# Port_Def.net
KiCad netlist of a schematic drawn in Altium Designer
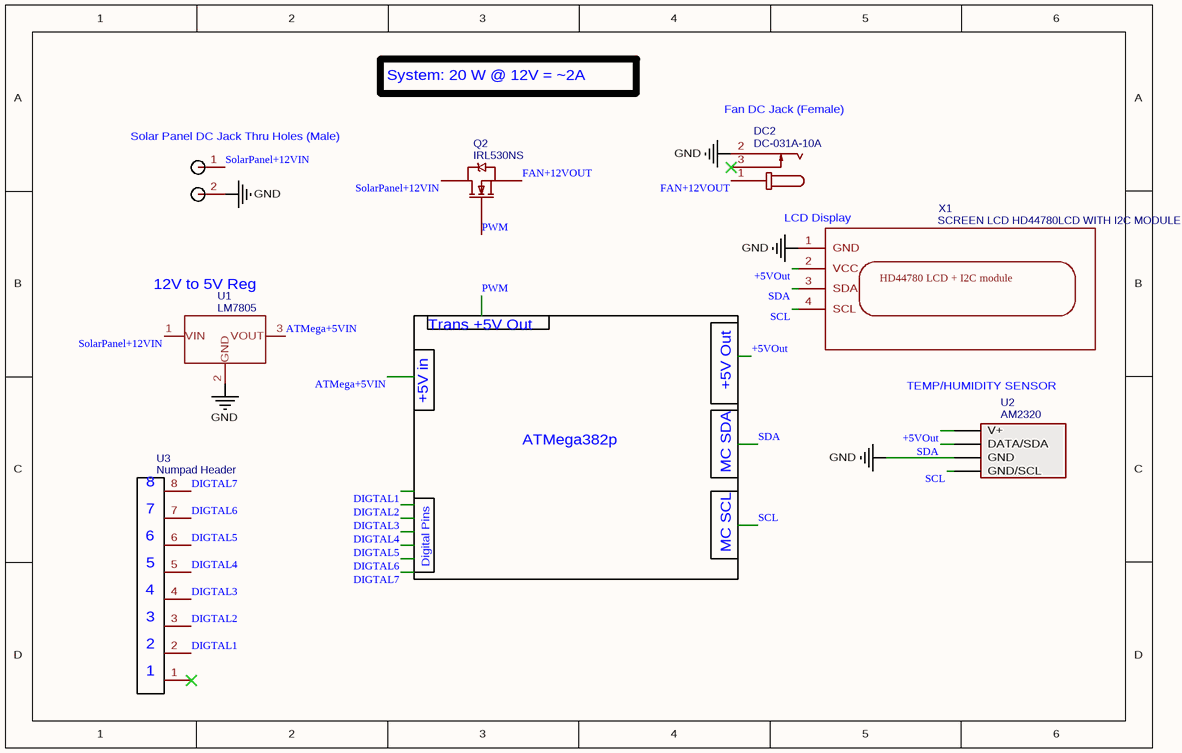
[diagram p0: Port Def.schdoc]

(export (version "E")
  (design (tool "Eeschema 10.0.6"))
  (components
    (comp (ref "DC2")
      (value "DC-031A-10A")
      (fields (field (name "BOM_SUPPLIER PART") "C145927") (field (name "CONTRIBUTOR") "LCSC"))
      (libsource (lib "altium-import") (part "root_2_DC-031A-10A_"))
    )
    (comp (ref "Q2")
      (value "IRL530NS")
      (description "HEXFET Power MOSFET")
      (libsource (lib "altium-import") (part "root_1_IRL530NS_"))
    )
    (comp (ref "U1")
      (value "LM7805")
      (description "DIP PMIC;LDO;Vin 7.5-20V;Adj;1A;Without En;1-Ch")
      (fields
        (field (name "BOM_SUPPLIER PART") "310030049")
        (field (name "BOM_MANUFACTURER PART") "LM7805ACT")
      )
      (libsource (lib "altium-import") (part "root_0_LM7805_"))
    )
    (comp (ref "U2")
      (value "AM2320")
      (fields
        (field (name "BOM_SUPPLIER PART") "E59481")
        (field (name "BOM_MANUFACTURER PART") "Header-Male-2.54_1x4")
      )
      (libsource (lib "altium-import") (part "root_0_AM2320_"))
    )
    (comp (ref "U3")
      (value "Numpad Header")
      (fields (field (name "CONTRIBUTOR") "iammuria"))
      (libsource (lib "altium-import") (part "root_2_Numpad Header_"))
    )
    (comp (ref "X1")
      (value "SCREEN LCD HD44780LCD WITH I2C MODULE")
      (fields (field (name "CONTRIBUTOR") "dartagnan586e"))
      (libsource (lib "altium-import") (part "root_0_SCREEN LCD HD44780LCD WITH I2C MODULE_"))
    )
    (comp (ref "XT1")
      (value "Pad")
      (fields (field (name "CONTRIBUTOR") "Artem_Kosorukov"))
      (libsource (lib "") (part "root_0_Pad__1"))
    )
    (comp (ref "XT2")
      (value "Pad")
      (fields (field (name "CONTRIBUTOR") "Artem_Kosorukov"))
      (libsource (lib "altium-import") (part "root_0_Pad_"))
    )
  )
  (nets
    (net (code "1") (name "/+5VOut") (class "Default")
      (node (ref "U2") (pin "1") (pinfunction "V+_1") (pintype "passive"))
      (node (ref "X1") (pin "2") (pinfunction "VCC_2") (pintype "passive"))
    )
    (net (code "2") (name "/ATMega+5VIN") (class "Default")
      (node (ref "U1") (pin "3") (pinfunction "VOUT_3") (pintype "passive"))
    )
    (net (code "10") (name "/FAN+12VOUT") (class "Default")
      (node (ref "DC2") (pin "1") (pinfunction "1_1") (pintype "passive"))
      (node (ref "Q2") (pin "3") (pinfunction "S_3") (pintype "passive"))
    )
    (net (code "11") (name "/PWM") (class "Default")
      (node (ref "Q2") (pin "1") (pinfunction "G_1") (pintype "passive"))
    )
    (net (code "12") (name "/SCL") (class "Default")
      (node (ref "U2") (pin "4") (pinfunction "GND/SCL_4") (pintype "passive"))
      (node (ref "X1") (pin "4") (pinfunction "SCL_4") (pintype "passive"))
    )
    (net (code "13") (name "/SDA") (class "Default")
      (node (ref "U2") (pin "2") (pinfunction "DATA/SDA_2") (pintype "passive"))
      (node (ref "X1") (pin "3") (pinfunction "SDA_3") (pintype "passive"))
    )
    (net (code "14") (name "/SolarPanel+12VIN") (class "Default")
      (node (ref "Q2") (pin "2") (pinfunction "D_2") (pintype "passive"))
      (node (ref "U1") (pin "1") (pinfunction "VIN_1") (pintype "passive"))
      (node (ref "XT1") (pin "1") (pinfunction "TH_Pad_1") (pintype "passive"))
    )
    (net (code "15") (name "GND") (class "Default")
      (node (ref "DC2") (pin "2") (pinfunction "2_2") (pintype "passive"))
      (node (ref "U1") (pin "2") (pinfunction "GND_2") (pintype "passive"))
      (node (ref "U2") (pin "3") (pinfunction "GND_3") (pintype "passive"))
      (node (ref "X1") (pin "1") (pinfunction "GND_1") (pintype "passive"))
      (node (ref "XT2") (pin "2") (pinfunction "TH_Pad_2") (pintype "passive"))
    )
    (net (code "16") (name "unconnected-(DC2-Pad3)") (class "Default")
      (node (ref "DC2") (pin "3") (pinfunction "3_3") (pintype "passive+no_connect"))
    )
    (net (code "17") (name "unconnected-(U3-Pad1)") (class "Default")
      (node (ref "U3") (pin "1") (pinfunction "1_1") (pintype "passive"))
    )
    (net (code "18") (name "unconnected-(U3-Pad2)") (class "Default")
      (node (ref "U3") (pin "2") (pinfunction "2_2") (pintype "passive"))
    )
    (net (code "19") (name "unconnected-(U3-Pad3)") (class "Default")
      (node (ref "U3") (pin "3") (pinfunction "3_3") (pintype "passive"))
    )
    (net (code "20") (name "unconnected-(U3-Pad4)") (class "Default")
      (node (ref "U3") (pin "4") (pinfunction "4_4") (pintype "passive"))
    )
    (net (code "21") (name "unconnected-(U3-Pad5)") (class "Default")
      (node (ref "U3") (pin "5") (pinfunction "5_5") (pintype "passive"))
    )
    (net (code "22") (name "unconnected-(U3-Pad6)") (class "Default")
      (node (ref "U3") (pin "6") (pinfunction "6_6") (pintype "passive"))
    )
    (net (code "23") (name "unconnected-(U3-Pad7)") (class "Default")
      (node (ref "U3") (pin "7") (pinfunction "7_7") (pintype "passive"))
    )
    (net (code "24") (name "unconnected-(U3-Pad8)") (class "Default")
      (node (ref "U3") (pin "8") (pinfunction "8_8") (pintype "passive"))
    )
  )
)
